# DCAR_Power.net
KiCad netlist of a schematic drawn in Altium Designer
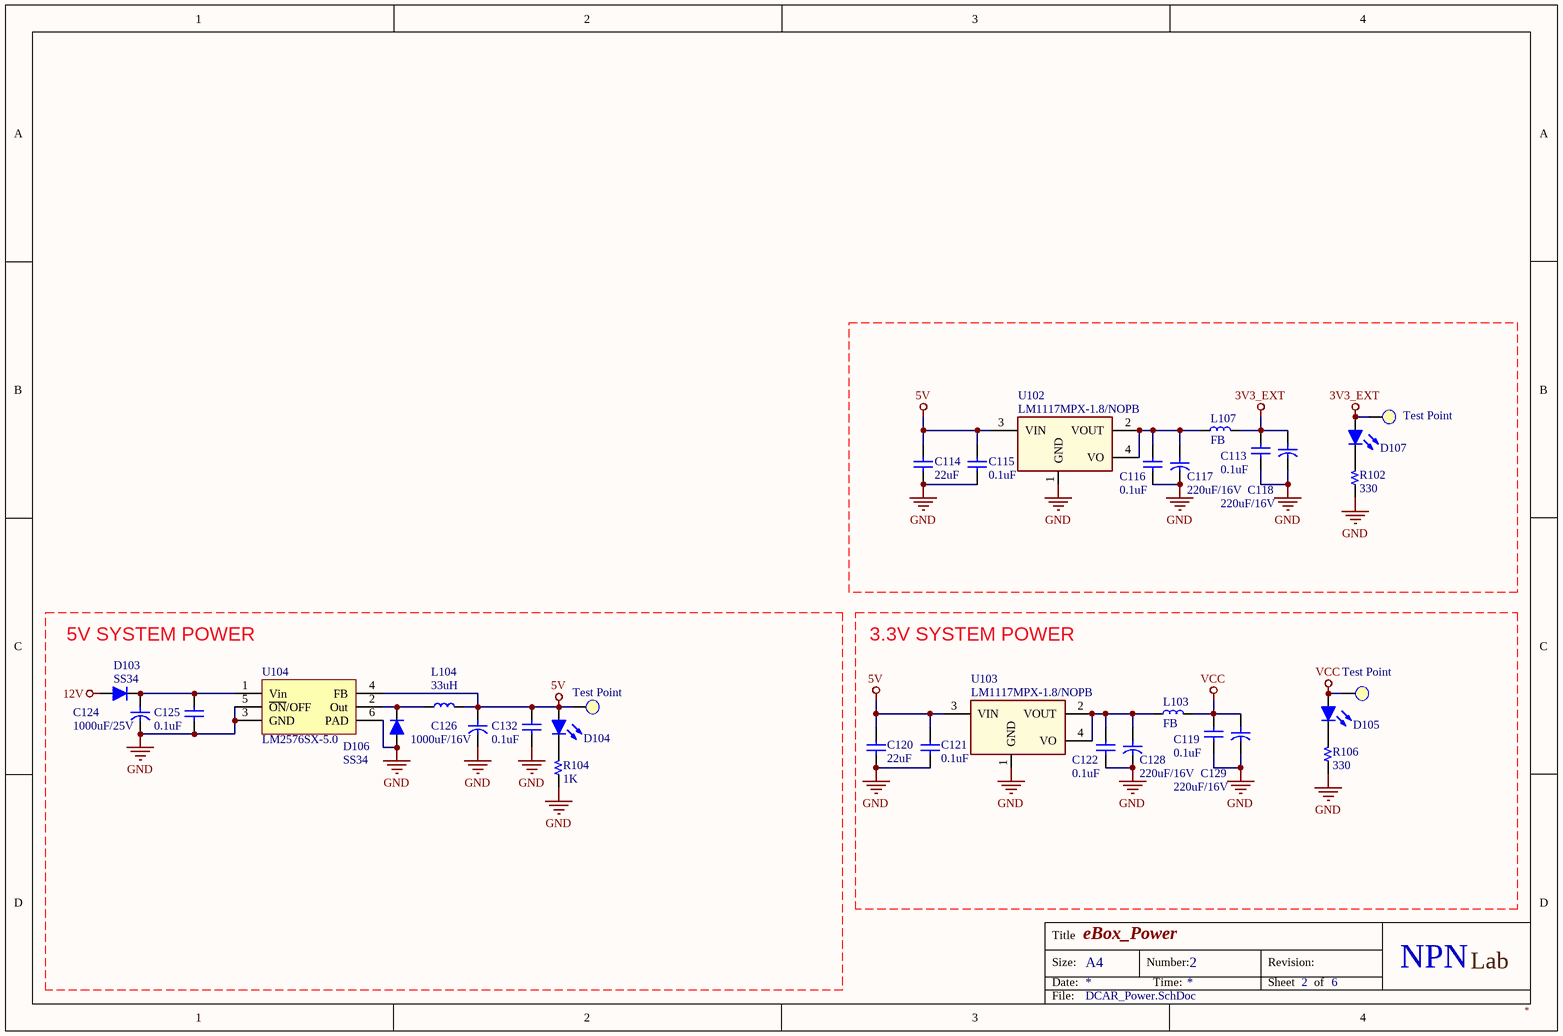
[diagram p0: DCAR_Power.SchDoc]

(export (version "E")
  (design (tool "Eeschema 10.0.6"))
  (components
    (comp (ref "3V3")
      (value "Test Point")
      (footprint "TestPoint/SMD/1.5mm")
      (libsource (lib "chipfc_altium_libs_extras") (part "Test Point"))
    )
    (comp (ref "5V")
      (value "Test Point")
      (footprint "TestPoint/SMD/1.5mm")
      (libsource (lib "chipfc_altium_libs_extras") (part "Test Point"))
    )
    (comp (ref "C113")
      (value "0.1uF")
      (footprint "C 0805")
      (description "CAP CER 0.1UF 50V X7R 0603")
      (libsource (lib "chipfc_altium_libs") (part "Capacitor NP"))
    )
    (comp (ref "C114")
      (value "22uF")
      (footprint "C 1210")
      (description "CAP CER 22UF 50V X7R 1210")
      (libsource (lib "chipfc_altium_libs") (part "Capacitor NP"))
    )
    (comp (ref "C115")
      (value "0.1uF")
      (footprint "C 0805")
      (description "CAP CER 0.1UF 50V X7R 0603")
      (libsource (lib "chipfc_altium_libs") (part "Capacitor NP"))
    )
    (comp (ref "C116")
      (value "0.1uF")
      (footprint "C 0805")
      (description "CAP CER 0.1UF 50V X7R 0603")
      (libsource (lib "chipfc_altium_libs") (part "Capacitor NP"))
    )
    (comp (ref "C117")
      (value "220uF/16V")
      (footprint "CYL/D.250/LS.100")
      (description "CAP TANT 100UF 20% 16V 2917")
      (libsource (lib "") (part "Capacitor_1"))
    )
    (comp (ref "C118")
      (value "220uF/16V")
      (footprint "CYL/D.250/LS.100")
      (description "CAP TANT 100UF 20% 16V 2917")
      (libsource (lib "") (part "Capacitor_1"))
    )
    (comp (ref "C119")
      (value "0.1uF")
      (footprint "C 0805")
      (description "CAP CER 0.1UF 50V X7R 0603")
      (libsource (lib "chipfc_altium_libs") (part "Capacitor NP"))
    )
    (comp (ref "C120")
      (value "22uF")
      (footprint "C 1210")
      (description "CAP CER 22UF 50V X7R 1210")
      (libsource (lib "chipfc_altium_libs") (part "Capacitor NP"))
    )
    (comp (ref "C121")
      (value "0.1uF")
      (footprint "C 0805")
      (description "CAP CER 0.1UF 50V X7R 0603")
      (libsource (lib "chipfc_altium_libs") (part "Capacitor NP"))
    )
    (comp (ref "C122")
      (value "0.1uF")
      (footprint "C 0805")
      (description "CAP CER 0.1UF 50V X7R 0603")
      (libsource (lib "chipfc_altium_libs") (part "Capacitor NP"))
    )
    (comp (ref "C124")
      (value "1000uF/25V")
      (footprint "CAP/D100/H200/LS50")
      (description "Capacitor pol")
      (libsource (lib "chipfc_altium_libs") (part "Capacitor"))
    )
    (comp (ref "C125")
      (value "0.1uF")
      (footprint "C 0805")
      (description "CAP CER 0.1UF 50V X7R 0805")
      (libsource (lib "chipfc_altium_libs") (part "Capacitor NP"))
    )
    (comp (ref "C126")
      (value "1000uF/16V")
      (footprint "CAP/D100/H200/LS50")
      (description "Capacitor pol")
      (libsource (lib "chipfc_altium_libs") (part "Capacitor"))
    )
    (comp (ref "C128")
      (value "220uF/16V")
      (footprint "CYL/D.250/LS.100")
      (description "CAP TANT 100UF 20% 16V 2917")
      (libsource (lib "") (part "Capacitor_1"))
    )
    (comp (ref "C129")
      (value "220uF/16V")
      (footprint "CYL/D.250/LS.100")
      (description "CAP TANT 100UF 20% 16V 2917")
      (libsource (lib "") (part "Capacitor_1"))
    )
    (comp (ref "C132")
      (value "0.1uF")
      (footprint "C 0805")
      (description "CAP CER 0.1UF 50V X7R 0805")
      (libsource (lib "chipfc_altium_libs") (part "Capacitor NP"))
    )
    (comp (ref "D103")
      (value "SS34")
      (footprint "DO-214AC (SMA) L")
      (description "Default Diode")
      (libsource (lib "chipfc_altium_libs") (part "Diode"))
    )
    (comp (ref "D104")
      (value "5V Led")
      (footprint "LED 3MM - red")
      (description "LED RED CLEAR 0603 SMD")
      (libsource (lib "chipfc_altium_libs") (part "Led"))
    )
    (comp (ref "D105")
      (value "5V Led")
      (footprint "LED 3MM - red")
      (description "LED RED CLEAR 0603 SMD")
      (libsource (lib "chipfc_altium_libs") (part "Led"))
    )
    (comp (ref "D106")
      (value "SS34")
      (footprint "DO-214AC (SMA) L")
      (description "Default Diode")
      (libsource (lib "chipfc_altium_libs") (part "Diode"))
    )
    (comp (ref "D107")
      (value "5V Led")
      (footprint "LED 3MM - red")
      (description "LED RED CLEAR 0603 SMD")
      (libsource (lib "chipfc_altium_libs") (part "Led"))
    )
    (comp (ref "L103")
      (value "FB")
      (footprint "L 0805 (2012)")
      (libsource (lib "chipfc_altium_libs") (part "Inductor"))
    )
    (comp (ref "L104")
      (value "33uH")
      (footprint "Inductor SMD 12x12x8")
      (description "Inductor")
      (libsource (lib "chipfc_altium_libs") (part "Inductor"))
    )
    (comp (ref "L107")
      (value "FB")
      (footprint "L 0805 (2012)")
      (libsource (lib "chipfc_altium_libs") (part "Inductor"))
    )
    (comp (ref "R102")
      (value "330")
      (footprint "R 0603")
      (description "RES SMD 330 OHM 1% 1/10W 0603")
      (libsource (lib "chipfc_altium_libs") (part "Resistor"))
    )
    (comp (ref "R104")
      (value "1K")
      (footprint "R 0603")
      (description "RES SMD 1K OHM 1% 1/10W 0603")
      (libsource (lib "chipfc_altium_libs") (part "Resistor"))
    )
    (comp (ref "R106")
      (value "330")
      (footprint "R 0603")
      (description "RES SMD 330 OHM 1% 1/10W 0603")
      (libsource (lib "chipfc_altium_libs") (part "Resistor"))
    )
    (comp (ref "U102")
      (value "LM1117MPX-1.8/NOPB")
      (footprint "SOT-223")
      (description "IC REG LINEAR 1.8V 800MA SOT223")
      (libsource (lib "chipfc_altium_libs") (part "AMS1117"))
    )
    (comp (ref "U103")
      (value "LM1117MPX-1.8/NOPB")
      (footprint "SOT-223")
      (description "IC REG LINEAR 1.8V 800MA SOT223")
      (libsource (lib "chipfc_altium_libs") (part "AMS1117"))
    )
    (comp (ref "U104")
      (value "LM2576SX-5.0")
      (footprint "TO-263-6")
      (description "IC REG BUCK 5V 3A TO263-5")
      (fields (field (name "PART NO") "LM2576SX-5.0/NOPB"))
      (libsource (lib "chipfc_altium_libs") (part "LM2576SX-5.0"))
    )
    (comp (ref "VCC")
      (value "Test Point")
      (footprint "TestPoint/SMD/1.5mm")
      (libsource (lib "chipfc_altium_libs_extras") (part "Test Point"))
    )
  )
  (nets
    (net (code "1") (name "3V3_EXT") (class "Default")
      (node (ref "3V3") (pin "1") (pinfunction "TP_1") (pintype "passive"))
      (node (ref "C113") (pin "1") (pinfunction "1_1") (pintype "passive"))
      (node (ref "C118") (pin "1") (pinfunction "1_1") (pintype "passive"))
      (node (ref "D107") (pin "1") (pinfunction "A_1") (pintype "passive"))
      (node (ref "L107") (pin "2") (pinfunction "2_2") (pintype "passive"))
    )
    (net (code "2") (name "5V") (class "Default")
      (node (ref "5V") (pin "1") (pinfunction "TP_1") (pintype "passive"))
      (node (ref "C114") (pin "1") (pinfunction "1_1") (pintype "passive"))
      (node (ref "C115") (pin "1") (pinfunction "1_1") (pintype "passive"))
      (node (ref "C120") (pin "1") (pinfunction "1_1") (pintype "passive"))
      (node (ref "C121") (pin "1") (pinfunction "1_1") (pintype "passive"))
      (node (ref "C126") (pin "1") (pinfunction "1_1") (pintype "passive"))
      (node (ref "C132") (pin "1") (pinfunction "1_1") (pintype "passive"))
      (node (ref "D104") (pin "1") (pinfunction "A_1") (pintype "passive"))
      (node (ref "L104") (pin "2") (pinfunction "2_2") (pintype "passive"))
      (node (ref "U102") (pin "3") (pinfunction "VIN_3") (pintype "power_in"))
      (node (ref "U103") (pin "3") (pinfunction "VIN_3") (pintype "power_in"))
      (node (ref "U104") (pin "4") (pinfunction "FB_4") (pintype "passive"))
    )
    (net (code "3") (name "12V") (class "Default")
      (node (ref "D103") (pin "1") (pinfunction "A_1") (pintype "passive"))
    )
    (net (code "4") (name "GND") (class "Default")
      (node (ref "C113") (pin "2") (pinfunction "2_2") (pintype "passive"))
      (node (ref "C114") (pin "2") (pinfunction "2_2") (pintype "passive"))
      (node (ref "C115") (pin "2") (pinfunction "2_2") (pintype "passive"))
      (node (ref "C116") (pin "2") (pinfunction "2_2") (pintype "passive"))
      (node (ref "C117") (pin "2") (pinfunction "2_2") (pintype "passive"))
      (node (ref "C118") (pin "2") (pinfunction "2_2") (pintype "passive"))
      (node (ref "C119") (pin "2") (pinfunction "2_2") (pintype "passive"))
      (node (ref "C120") (pin "2") (pinfunction "2_2") (pintype "passive"))
      (node (ref "C121") (pin "2") (pinfunction "2_2") (pintype "passive"))
      (node (ref "C122") (pin "2") (pinfunction "2_2") (pintype "passive"))
      (node (ref "C124") (pin "2") (pinfunction "2_2") (pintype "passive"))
      (node (ref "C125") (pin "2") (pinfunction "2_2") (pintype "passive"))
      (node (ref "C126") (pin "2") (pinfunction "2_2") (pintype "passive"))
      (node (ref "C128") (pin "2") (pinfunction "2_2") (pintype "passive"))
      (node (ref "C129") (pin "2") (pinfunction "2_2") (pintype "passive"))
      (node (ref "C132") (pin "2") (pinfunction "2_2") (pintype "passive"))
      (node (ref "D106") (pin "1") (pinfunction "A_1") (pintype "passive"))
      (node (ref "R102") (pin "1") (pinfunction "1_1") (pintype "passive"))
      (node (ref "R104") (pin "1") (pinfunction "1_1") (pintype "passive"))
      (node (ref "R106") (pin "1") (pinfunction "1_1") (pintype "passive"))
      (node (ref "U102") (pin "1") (pinfunction "GND_1") (pintype "passive"))
      (node (ref "U103") (pin "1") (pinfunction "GND_1") (pintype "passive"))
      (node (ref "U104") (pin "3") (pinfunction "GND_3") (pintype "passive"))
      (node (ref "U104") (pin "5") (pinfunction "~{ON}/OFF_5") (pintype "passive"))
      (node (ref "U104") (pin "6") (pinfunction "PAD_6") (pintype "passive"))
    )
    (net (code "5") (name "Net-(D103-K)") (class "Default")
      (node (ref "C124") (pin "1") (pinfunction "1_1") (pintype "passive"))
      (node (ref "C125") (pin "1") (pinfunction "1_1") (pintype "passive"))
      (node (ref "D103") (pin "2") (pinfunction "K_2") (pintype "passive"))
      (node (ref "U104") (pin "1") (pinfunction "Vin_1") (pintype "passive"))
    )
    (net (code "6") (name "Net-(D104-K)") (class "Default")
      (node (ref "D104") (pin "2") (pinfunction "K_2") (pintype "passive"))
      (node (ref "R104") (pin "2") (pinfunction "2_2") (pintype "passive"))
    )
    (net (code "7") (name "Net-(D105-K)") (class "Default")
      (node (ref "D105") (pin "2") (pinfunction "K_2") (pintype "passive"))
      (node (ref "R106") (pin "2") (pinfunction "2_2") (pintype "passive"))
    )
    (net (code "8") (name "Net-(D106-K)") (class "Default")
      (node (ref "D106") (pin "2") (pinfunction "K_2") (pintype "passive"))
      (node (ref "L104") (pin "1") (pinfunction "1_1") (pintype "passive"))
      (node (ref "U104") (pin "2") (pinfunction "Out_2") (pintype "passive"))
    )
    (net (code "9") (name "Net-(D107-K)") (class "Default")
      (node (ref "D107") (pin "2") (pinfunction "K_2") (pintype "passive"))
      (node (ref "R102") (pin "2") (pinfunction "2_2") (pintype "passive"))
    )
    (net (code "10") (name "Net-(U102-VO)") (class "Default")
      (node (ref "C116") (pin "1") (pinfunction "1_1") (pintype "passive"))
      (node (ref "C117") (pin "1") (pinfunction "1_1") (pintype "passive"))
      (node (ref "L107") (pin "1") (pinfunction "1_1") (pintype "passive"))
      (node (ref "U102") (pin "2") (pinfunction "VOUT_2") (pintype "passive"))
      (node (ref "U102") (pin "4") (pinfunction "VO_4") (pintype "passive"))
    )
    (net (code "11") (name "Net-(U103-VO)") (class "Default")
      (node (ref "C122") (pin "1") (pinfunction "1_1") (pintype "passive"))
      (node (ref "C128") (pin "1") (pinfunction "1_1") (pintype "passive"))
      (node (ref "L103") (pin "1") (pinfunction "1_1") (pintype "passive"))
      (node (ref "U103") (pin "2") (pinfunction "VOUT_2") (pintype "passive"))
      (node (ref "U103") (pin "4") (pinfunction "VO_4") (pintype "passive"))
    )
    (net (code "12") (name "VCC") (class "Default")
      (node (ref "C119") (pin "1") (pinfunction "1_1") (pintype "passive"))
      (node (ref "C129") (pin "1") (pinfunction "1_1") (pintype "passive"))
      (node (ref "D105") (pin "1") (pinfunction "A_1") (pintype "passive"))
      (node (ref "L103") (pin "2") (pinfunction "2_2") (pintype "passive"))
      (node (ref "VCC") (pin "1") (pinfunction "TP_1") (pintype "passive"))
    )
  )
)
